# circuitPendulumController.net
KiCad netlist of a schematic drawn in EAGLE
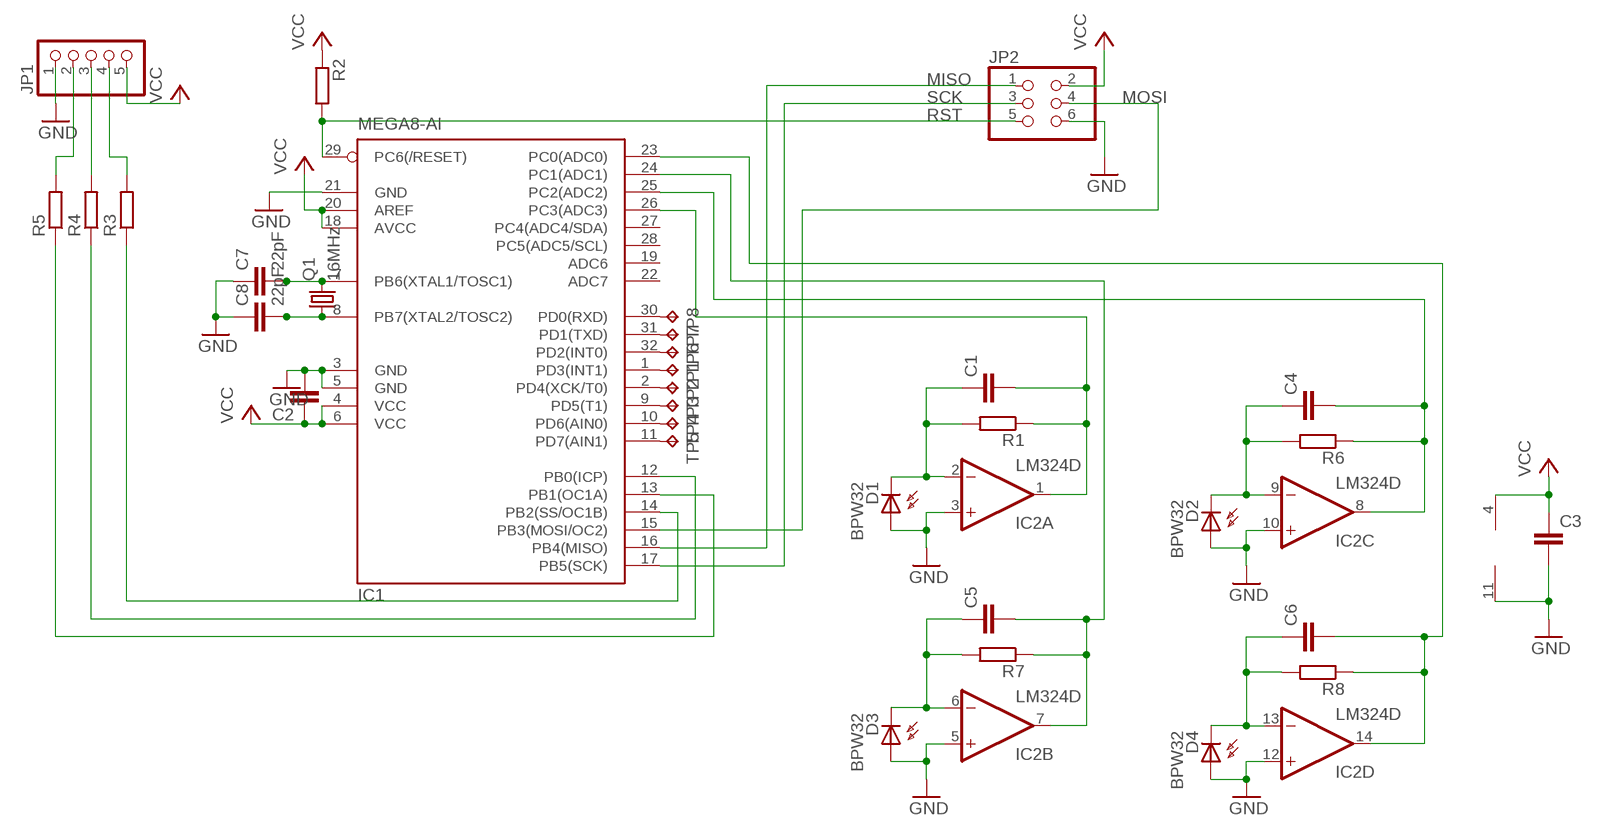
[diagram p0: schematic, sheet 1]

(export (version "E")
  (design (tool "Eeschema 10.0.6"))
  (components
    (comp (ref "C1")
      (value "C-EUC0603")
      (footprint "eagle-import:C0603")
      (libsource (lib "eagle-import") (part "C-EUC0603"))
    )
    (comp (ref "C2")
      (value "C-EUC0603")
      (footprint "eagle-import:C0603")
      (libsource (lib "eagle-import") (part "C-EUC0603"))
    )
    (comp (ref "C3")
      (value "C-EUC0603")
      (footprint "eagle-import:C0603")
      (libsource (lib "eagle-import") (part "C-EUC0603"))
    )
    (comp (ref "C4")
      (value "C-EUC0603")
      (footprint "eagle-import:C0603")
      (libsource (lib "eagle-import") (part "C-EUC0603"))
    )
    (comp (ref "C5")
      (value "C-EUC0603")
      (footprint "eagle-import:C0603")
      (libsource (lib "eagle-import") (part "C-EUC0603"))
    )
    (comp (ref "C6")
      (value "C-EUC0603")
      (footprint "eagle-import:C0603")
      (libsource (lib "eagle-import") (part "C-EUC0603"))
    )
    (comp (ref "C7")
      (value "22pF")
      (footprint "eagle-import:C0603")
      (libsource (lib "eagle-import") (part "C-EUC0603"))
    )
    (comp (ref "C8")
      (value "22pF")
      (footprint "eagle-import:C0603")
      (libsource (lib "eagle-import") (part "C-EUC0603"))
    )
    (comp (ref "D1")
      (value "BPW32")
      (footprint "eagle-import:BPW32")
      (libsource (lib "eagle-import") (part "BPW32"))
    )
    (comp (ref "D2")
      (value "BPW32")
      (footprint "eagle-import:BPW32")
      (libsource (lib "eagle-import") (part "BPW32"))
    )
    (comp (ref "D3")
      (value "BPW32")
      (footprint "eagle-import:BPW32")
      (libsource (lib "eagle-import") (part "BPW32"))
    )
    (comp (ref "D4")
      (value "BPW32")
      (footprint "eagle-import:BPW32")
      (libsource (lib "eagle-import") (part "BPW32"))
    )
    (comp (ref "IC1")
      (value "MEGA8-AI")
      (footprint "eagle-import:TQFP32-08")
      (fields (field (name "MPN") "ATMEGA8-16AU"))
      (libsource (lib "eagle-import") (part "MEGA8-AI"))
    )
    (comp (ref "IC2")
      (value "LM324D")
      (footprint "eagle-import:SO14")
      (libsource (lib "eagle-import") (part "LM324D"))
    )
    (comp (ref "JP1")
      (value "PINHD-1X55X2MM")
      (footprint "eagle-import:1_05X2MM")
      (libsource (lib "eagle-import") (part "PINHD-1X55X2MM"))
    )
    (comp (ref "JP2")
      (value "PINHD-2X3")
      (footprint "eagle-import:2X03")
      (libsource (lib "eagle-import") (part "PINHD-2X3"))
    )
    (comp (ref "Q1")
      (value "16MHz")
      (footprint "eagle-import:HC49_S")
      (libsource (lib "eagle-import") (part "CRYSTALHC49S"))
    )
    (comp (ref "R1")
      (value "R-EU_R0603")
      (footprint "eagle-import:R0603")
      (libsource (lib "eagle-import") (part "R-EU_R0603"))
    )
    (comp (ref "R2")
      (value "R-EU_R0603")
      (footprint "eagle-import:R0603")
      (libsource (lib "eagle-import") (part "R-EU_R0603"))
    )
    (comp (ref "R3")
      (value "R-EU_R0603")
      (footprint "eagle-import:R0603")
      (libsource (lib "eagle-import") (part "R-EU_R0603"))
    )
    (comp (ref "R4")
      (value "R-EU_R0603")
      (footprint "eagle-import:R0603")
      (libsource (lib "eagle-import") (part "R-EU_R0603"))
    )
    (comp (ref "R5")
      (value "R-EU_R0603")
      (footprint "eagle-import:R0603")
      (libsource (lib "eagle-import") (part "R-EU_R0603"))
    )
    (comp (ref "R6")
      (value "R-EU_R0603")
      (footprint "eagle-import:R0603")
      (libsource (lib "eagle-import") (part "R-EU_R0603"))
    )
    (comp (ref "R7")
      (value "R-EU_R0603")
      (footprint "eagle-import:R0603")
      (libsource (lib "eagle-import") (part "R-EU_R0603"))
    )
    (comp (ref "R8")
      (value "R-EU_R0603")
      (footprint "eagle-import:R0603")
      (libsource (lib "eagle-import") (part "R-EU_R0603"))
    )
    (comp (ref "TP1")
      (value "TPTP11R")
      (footprint "eagle-import:TP11R")
      (libsource (lib "eagle-import") (part "TPTP11R"))
    )
    (comp (ref "TP2")
      (value "TPTP11R")
      (footprint "eagle-import:TP11R")
      (libsource (lib "eagle-import") (part "TPTP11R"))
    )
    (comp (ref "TP3")
      (value "TPTP11R")
      (footprint "eagle-import:TP11R")
      (libsource (lib "eagle-import") (part "TPTP11R"))
    )
    (comp (ref "TP4")
      (value "TPTP11R")
      (footprint "eagle-import:TP11R")
      (libsource (lib "eagle-import") (part "TPTP11R"))
    )
    (comp (ref "TP5")
      (value "TPTP11R")
      (footprint "eagle-import:TP11R")
      (libsource (lib "eagle-import") (part "TPTP11R"))
    )
    (comp (ref "TP6")
      (value "TPTP11R")
      (footprint "eagle-import:TP11R")
      (libsource (lib "eagle-import") (part "TPTP11R"))
    )
    (comp (ref "TP7")
      (value "TPTP11R")
      (footprint "eagle-import:TP11R")
      (libsource (lib "eagle-import") (part "TPTP11R"))
    )
    (comp (ref "TP8")
      (value "TPTP11R")
      (footprint "eagle-import:TP11R")
      (libsource (lib "eagle-import") (part "TPTP11R"))
    )
  )
  (nets
    (net (code "1") (name "/MISO") (class "Default")
      (node (ref "IC1") (pin "16") (pinfunction "PB4(MISO)_16") (pintype "bidirectional"))
      (node (ref "JP2") (pin "1") (pinfunction "1_1") (pintype "passive"))
    )
    (net (code "2") (name "/MOSI") (class "Default")
      (node (ref "IC1") (pin "15") (pinfunction "PB3(MOSI/OC2)_15") (pintype "bidirectional"))
      (node (ref "JP2") (pin "4") (pinfunction "4_4") (pintype "passive"))
    )
    (net (code "3") (name "/RST") (class "Default")
      (node (ref "IC1") (pin "29") (pinfunction "PC6(/RESET)_29") (pintype "bidirectional"))
      (node (ref "JP2") (pin "5") (pinfunction "5_5") (pintype "passive"))
      (node (ref "R2") (pin "2") (pinfunction "2_2") (pintype "passive"))
    )
    (net (code "4") (name "/SCK") (class "Default")
      (node (ref "IC1") (pin "17") (pinfunction "PB5(SCK)_17") (pintype "bidirectional"))
      (node (ref "JP2") (pin "3") (pinfunction "3_3") (pintype "passive"))
    )
    (net (code "5") (name "GND") (class "Default")
      (node (ref "C2") (pin "2") (pinfunction "2_2") (pintype "passive"))
      (node (ref "C3") (pin "2") (pinfunction "2_2") (pintype "passive"))
      (node (ref "C7") (pin "1") (pinfunction "1_1") (pintype "passive"))
      (node (ref "C8") (pin "1") (pinfunction "1_1") (pintype "passive"))
      (node (ref "D1") (pin "A") (pinfunction "A_A") (pintype "passive"))
      (node (ref "D2") (pin "A") (pinfunction "A_A") (pintype "passive"))
      (node (ref "D3") (pin "A") (pinfunction "A_A") (pintype "passive"))
      (node (ref "D4") (pin "A") (pinfunction "A_A") (pintype "passive"))
      (node (ref "IC1") (pin "21") (pinfunction "GND_21") (pintype "power_in"))
      (node (ref "IC1") (pin "3") (pinfunction "GND_3") (pintype "power_in"))
      (node (ref "IC1") (pin "5") (pinfunction "GND_5") (pintype "power_in"))
      (node (ref "IC2") (pin "10") (pinfunction "+IN_10") (pintype "input"))
      (node (ref "IC2") (pin "11") (pinfunction "V-_11") (pintype "power_in"))
      (node (ref "IC2") (pin "12") (pinfunction "+IN_12") (pintype "input"))
      (node (ref "IC2") (pin "3") (pinfunction "+IN_3") (pintype "input"))
      (node (ref "IC2") (pin "5") (pinfunction "+IN_5") (pintype "input"))
      (node (ref "JP1") (pin "1") (pinfunction "1_1") (pintype "passive"))
      (node (ref "JP2") (pin "6") (pinfunction "6_6") (pintype "passive"))
    )
    (net (code "6") (name "Net-(D1-C)") (class "Default")
      (node (ref "C1") (pin "1") (pinfunction "1_1") (pintype "passive"))
      (node (ref "D1") (pin "K") (pinfunction "C_K") (pintype "passive"))
      (node (ref "IC2") (pin "2") (pinfunction "-IN_2") (pintype "input"))
      (node (ref "R1") (pin "2") (pinfunction "2_2") (pintype "passive"))
    )
    (net (code "7") (name "Net-(D2-C)") (class "Default")
      (node (ref "C4") (pin "1") (pinfunction "1_1") (pintype "passive"))
      (node (ref "D2") (pin "K") (pinfunction "C_K") (pintype "passive"))
      (node (ref "IC2") (pin "9") (pinfunction "-IN_9") (pintype "input"))
      (node (ref "R6") (pin "2") (pinfunction "2_2") (pintype "passive"))
    )
    (net (code "8") (name "Net-(D3-C)") (class "Default")
      (node (ref "C5") (pin "1") (pinfunction "1_1") (pintype "passive"))
      (node (ref "D3") (pin "K") (pinfunction "C_K") (pintype "passive"))
      (node (ref "IC2") (pin "6") (pinfunction "-IN_6") (pintype "input"))
      (node (ref "R7") (pin "2") (pinfunction "2_2") (pintype "passive"))
    )
    (net (code "9") (name "Net-(D4-C)") (class "Default")
      (node (ref "C6") (pin "1") (pinfunction "1_1") (pintype "passive"))
      (node (ref "D4") (pin "K") (pinfunction "C_K") (pintype "passive"))
      (node (ref "IC2") (pin "13") (pinfunction "-IN_13") (pintype "input"))
      (node (ref "R8") (pin "2") (pinfunction "2_2") (pintype "passive"))
    )
    (net (code "10") (name "Net-(IC1-PB0(ICP))") (class "Default")
      (node (ref "IC1") (pin "12") (pinfunction "PB0(ICP)_12") (pintype "bidirectional"))
      (node (ref "R4") (pin "1") (pinfunction "1_1") (pintype "passive"))
    )
    (net (code "11") (name "Net-(IC1-PB1(OC1A))") (class "Default")
      (node (ref "IC1") (pin "13") (pinfunction "PB1(OC1A)_13") (pintype "bidirectional"))
      (node (ref "R5") (pin "1") (pinfunction "1_1") (pintype "passive"))
    )
    (net (code "12") (name "Net-(IC1-PB2(SS{slash}OC1B))") (class "Default")
      (node (ref "IC1") (pin "14") (pinfunction "PB2(SS/OC1B)_14") (pintype "bidirectional"))
      (node (ref "R3") (pin "1") (pinfunction "1_1") (pintype "passive"))
    )
    (net (code "13") (name "Net-(IC1-PB6(XTAL1{slash}TOSC1))") (class "Default")
      (node (ref "C7") (pin "2") (pinfunction "2_2") (pintype "passive"))
      (node (ref "IC1") (pin "7") (pinfunction "PB6(XTAL1/TOSC1)_7") (pintype "bidirectional"))
      (node (ref "Q1") (pin "2") (pinfunction "2_2") (pintype "passive"))
    )
    (net (code "14") (name "Net-(IC1-PB7(XTAL2{slash}TOSC2))") (class "Default")
      (node (ref "C8") (pin "2") (pinfunction "2_2") (pintype "passive"))
      (node (ref "IC1") (pin "8") (pinfunction "PB7(XTAL2/TOSC2)_8") (pintype "bidirectional"))
      (node (ref "Q1") (pin "1") (pinfunction "1_1") (pintype "passive"))
    )
    (net (code "15") (name "Net-(IC1-PC0(ADC0))") (class "Default")
      (node (ref "C6") (pin "2") (pinfunction "2_2") (pintype "passive"))
      (node (ref "IC1") (pin "23") (pinfunction "PC0(ADC0)_23") (pintype "bidirectional"))
      (node (ref "IC2") (pin "14") (pinfunction "OUT_14") (pintype "output"))
      (node (ref "R8") (pin "1") (pinfunction "1_1") (pintype "passive"))
    )
    (net (code "16") (name "Net-(IC1-PC1(ADC1))") (class "Default")
      (node (ref "C5") (pin "2") (pinfunction "2_2") (pintype "passive"))
      (node (ref "IC1") (pin "24") (pinfunction "PC1(ADC1)_24") (pintype "bidirectional"))
      (node (ref "IC2") (pin "7") (pinfunction "OUT_7") (pintype "output"))
      (node (ref "R7") (pin "1") (pinfunction "1_1") (pintype "passive"))
    )
    (net (code "17") (name "Net-(IC1-PC2(ADC2))") (class "Default")
      (node (ref "C4") (pin "2") (pinfunction "2_2") (pintype "passive"))
      (node (ref "IC1") (pin "25") (pinfunction "PC2(ADC2)_25") (pintype "bidirectional"))
      (node (ref "IC2") (pin "8") (pinfunction "OUT_8") (pintype "output"))
      (node (ref "R6") (pin "1") (pinfunction "1_1") (pintype "passive"))
    )
    (net (code "18") (name "Net-(IC1-PC3(ADC3))") (class "Default")
      (node (ref "C1") (pin "2") (pinfunction "2_2") (pintype "passive"))
      (node (ref "IC1") (pin "26") (pinfunction "PC3(ADC3)_26") (pintype "bidirectional"))
      (node (ref "IC2") (pin "1") (pinfunction "OUT_1") (pintype "output"))
      (node (ref "R1") (pin "1") (pinfunction "1_1") (pintype "passive"))
    )
    (net (code "19") (name "Net-(IC1-PD0(RXD))") (class "Default")
      (node (ref "IC1") (pin "30") (pinfunction "PD0(RXD)_30") (pintype "bidirectional"))
      (node (ref "TP8") (pin "TP") (pinfunction "TP_TP") (pintype "input"))
    )
    (net (code "20") (name "Net-(IC1-PD1(TXD))") (class "Default")
      (node (ref "IC1") (pin "31") (pinfunction "PD1(TXD)_31") (pintype "bidirectional"))
      (node (ref "TP7") (pin "TP") (pinfunction "TP_TP") (pintype "input"))
    )
    (net (code "21") (name "Net-(IC1-PD2(INT0))") (class "Default")
      (node (ref "IC1") (pin "32") (pinfunction "PD2(INT0)_32") (pintype "bidirectional"))
      (node (ref "TP6") (pin "TP") (pinfunction "TP_TP") (pintype "input"))
    )
    (net (code "22") (name "Net-(IC1-PD3(INT1))") (class "Default")
      (node (ref "IC1") (pin "1") (pinfunction "PD3(INT1)_1") (pintype "bidirectional"))
      (node (ref "TP1") (pin "TP") (pinfunction "TP_TP") (pintype "input"))
    )
    (net (code "23") (name "Net-(IC1-PD4(XCK{slash}T0))") (class "Default")
      (node (ref "IC1") (pin "2") (pinfunction "PD4(XCK/T0)_2") (pintype "bidirectional"))
      (node (ref "TP2") (pin "TP") (pinfunction "TP_TP") (pintype "input"))
    )
    (net (code "24") (name "Net-(IC1-PD5(T1))") (class "Default")
      (node (ref "IC1") (pin "9") (pinfunction "PD5(T1)_9") (pintype "bidirectional"))
      (node (ref "TP3") (pin "TP") (pinfunction "TP_TP") (pintype "input"))
    )
    (net (code "25") (name "Net-(IC1-PD6(AIN0))") (class "Default")
      (node (ref "IC1") (pin "10") (pinfunction "PD6(AIN0)_10") (pintype "bidirectional"))
      (node (ref "TP4") (pin "TP") (pinfunction "TP_TP") (pintype "input"))
    )
    (net (code "26") (name "Net-(IC1-PD7(AIN1))") (class "Default")
      (node (ref "IC1") (pin "11") (pinfunction "PD7(AIN1)_11") (pintype "bidirectional"))
      (node (ref "TP5") (pin "TP") (pinfunction "TP_TP") (pintype "input"))
    )
    (net (code "27") (name "Net-(JP1-Pad2)") (class "Default")
      (node (ref "JP1") (pin "2") (pinfunction "2_2") (pintype "passive"))
      (node (ref "R5") (pin "2") (pinfunction "2_2") (pintype "passive"))
    )
    (net (code "28") (name "Net-(JP1-Pad3)") (class "Default")
      (node (ref "JP1") (pin "3") (pinfunction "3_3") (pintype "passive"))
      (node (ref "R4") (pin "2") (pinfunction "2_2") (pintype "passive"))
    )
    (net (code "29") (name "Net-(JP1-Pad4)") (class "Default")
      (node (ref "JP1") (pin "4") (pinfunction "4_4") (pintype "passive"))
      (node (ref "R3") (pin "2") (pinfunction "2_2") (pintype "passive"))
    )
    (net (code "30") (name "VCC") (class "Default")
      (node (ref "C2") (pin "1") (pinfunction "1_1") (pintype "passive"))
      (node (ref "C3") (pin "1") (pinfunction "1_1") (pintype "passive"))
      (node (ref "IC1") (pin "18") (pinfunction "AVCC_18") (pintype "power_in"))
      (node (ref "IC1") (pin "20") (pinfunction "AREF_20") (pintype "passive"))
      (node (ref "IC1") (pin "4") (pinfunction "VCC_4") (pintype "power_in"))
      (node (ref "IC1") (pin "6") (pinfunction "VCC_6") (pintype "power_in"))
      (node (ref "IC2") (pin "4") (pinfunction "V+_4") (pintype "power_in"))
      (node (ref "JP1") (pin "5") (pinfunction "5_5") (pintype "passive"))
      (node (ref "JP2") (pin "2") (pinfunction "2_2") (pintype "passive"))
      (node (ref "R2") (pin "1") (pinfunction "1_1") (pintype "passive"))
    )
    (net (code "31") (name "unconnected-(IC1-ADC6-Pad19)") (class "Default")
      (node (ref "IC1") (pin "19") (pinfunction "ADC6_19") (pintype "bidirectional"))
    )
    (net (code "32") (name "unconnected-(IC1-ADC7-Pad22)") (class "Default")
      (node (ref "IC1") (pin "22") (pinfunction "ADC7_22") (pintype "bidirectional"))
    )
    (net (code "33") (name "unconnected-(IC1-PC4(ADC4{slash}SDA)-Pad27)") (class "Default")
      (node (ref "IC1") (pin "27") (pinfunction "PC4(ADC4/SDA)_27") (pintype "bidirectional"))
    )
    (net (code "34") (name "unconnected-(IC1-PC5(ADC5{slash}SCL)-Pad28)") (class "Default")
      (node (ref "IC1") (pin "28") (pinfunction "PC5(ADC5/SCL)_28") (pintype "bidirectional"))
    )
  )
)
